# C210_0004_MAX_Module_220601.net
KiCad netlist of a schematic drawn in Altium Designer
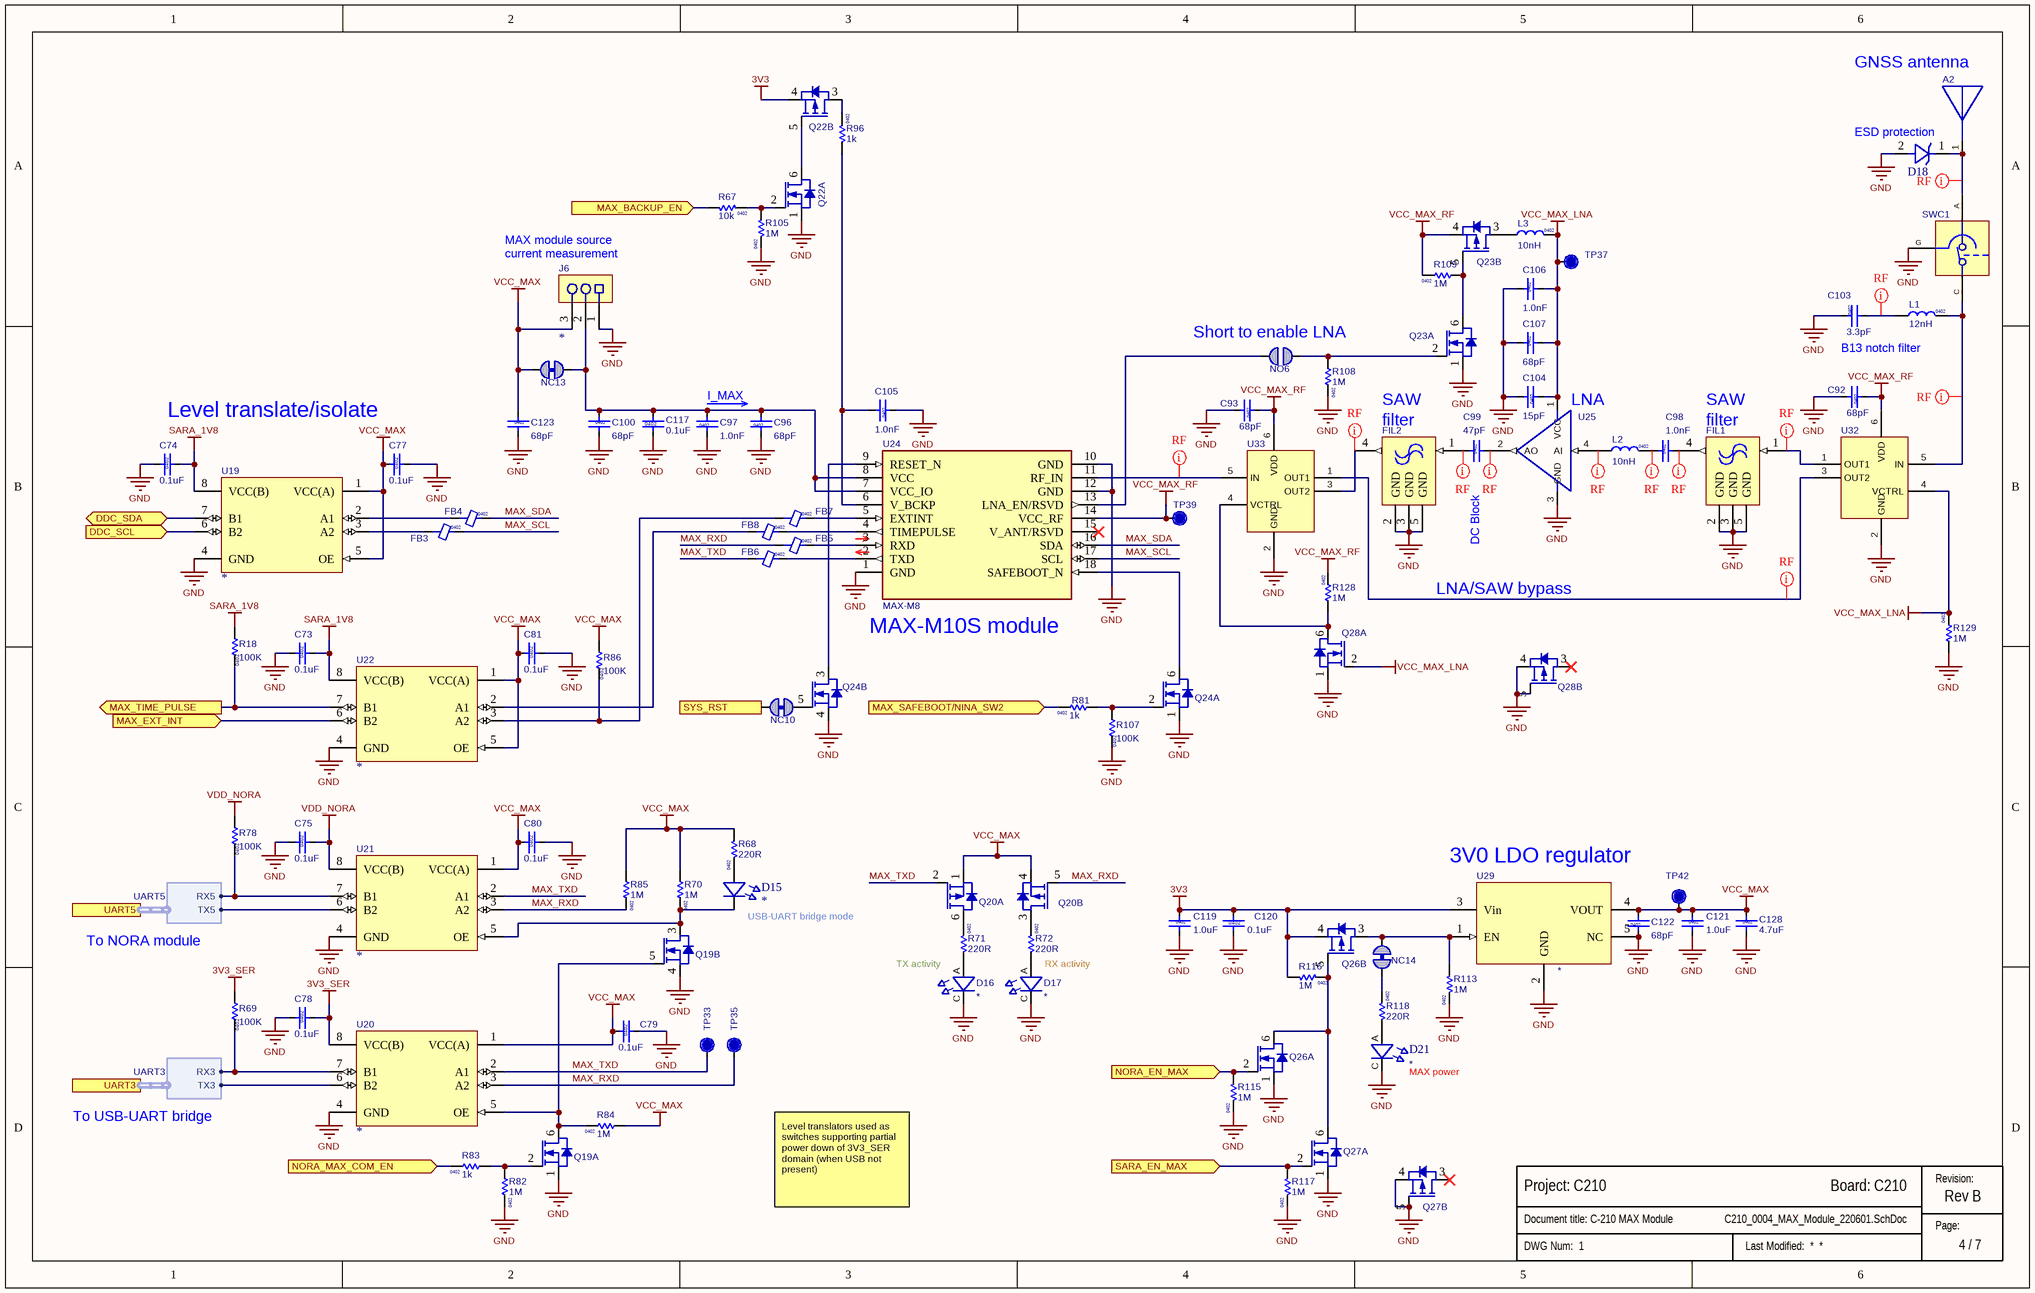
[diagram p0: C210_0004_MAX_Module_220601.SchDoc]

(export (version "E")
  (design (tool "Eeschema 10.0.6"))
  (components
    (comp (ref "A2")
      (value "CGGP.25.4.E.02")
      (footprint "CGGP.25.4.E.02")
      (description "ANT, THROUGH-HOLE, PATCH, GNSS, BEIDOU, GLONASS, GPS, 5dBi, 25MMx35MMx4MM")
      (libsource (lib "CGGP.25.4.E.02") (part "CGGP.25.4.E.02"))
    )
    (comp (ref "C73")
      (value "0.1uF")
      (footprint "Cap 0402 HD")
      (description "Cap, Ceramic 0.1uF 10V 10% X5R 0402")
      (fields
        (field (name "SIZE") "0402")
        (field (name "PART NUMBER") "120-00016")
        (field (name "MANUFACTURER") "Murata Electronics North America")
      )
      (libsource (lib "Arena_Parts_DB_Lib") (part "Cap Chip"))
    )
    (comp (ref "C74")
      (value "0.1uF")
      (footprint "Cap 0402 HD")
      (description "Cap, Ceramic 0.1uF 10V 10% X5R 0402")
      (fields
        (field (name "SIZE") "0402")
        (field (name "PART NUMBER") "120-00016")
        (field (name "MANUFACTURER") "Murata Electronics North America")
      )
      (libsource (lib "Arena_Parts_DB_Lib") (part "Cap Chip"))
    )
    (comp (ref "C75")
      (value "0.1uF")
      (footprint "Cap 0402 HD")
      (description "Cap, Ceramic 0.1uF 10V 10% X5R 0402")
      (fields
        (field (name "SIZE") "0402")
        (field (name "PART NUMBER") "120-00016")
        (field (name "MANUFACTURER") "Murata Electronics North America")
      )
      (libsource (lib "Arena_Parts_DB_Lib") (part "Cap Chip"))
    )
    (comp (ref "C77")
      (value "0.1uF")
      (footprint "Cap 0402 HD")
      (description "Cap, Ceramic 0.1uF 10V 10% X5R 0402")
      (fields
        (field (name "SIZE") "0402")
        (field (name "PART NUMBER") "120-00016")
        (field (name "MANUFACTURER") "Murata Electronics North America")
      )
      (libsource (lib "Arena_Parts_DB_Lib") (part "Cap Chip"))
    )
    (comp (ref "C78")
      (value "0.1uF")
      (footprint "Cap 0402 HD")
      (description "Cap, Ceramic 0.1uF 10V 10% X5R 0402")
      (fields
        (field (name "SIZE") "0402")
        (field (name "PART NUMBER") "120-00016")
        (field (name "MANUFACTURER") "Murata Electronics North America")
      )
      (libsource (lib "Arena_Parts_DB_Lib") (part "Cap Chip"))
    )
    (comp (ref "C79")
      (value "0.1uF")
      (footprint "Cap 0402 HD")
      (description "Cap, Ceramic 0.1uF 10V 10% X5R 0402")
      (fields
        (field (name "SIZE") "0402")
        (field (name "PART NUMBER") "120-00016")
        (field (name "MANUFACTURER") "Murata Electronics North America")
      )
      (libsource (lib "Arena_Parts_DB_Lib") (part "Cap Chip"))
    )
    (comp (ref "C80")
      (value "0.1uF")
      (footprint "Cap 0402 HD")
      (description "Cap, Ceramic 0.1uF 10V 10% X5R 0402")
      (fields
        (field (name "SIZE") "0402")
        (field (name "PART NUMBER") "120-00016")
        (field (name "MANUFACTURER") "Murata Electronics North America")
      )
      (libsource (lib "Arena_Parts_DB_Lib") (part "Cap Chip"))
    )
    (comp (ref "C81")
      (value "0.1uF")
      (footprint "Cap 0402 HD")
      (description "Cap, Ceramic 0.1uF 10V 10% X5R 0402")
      (fields
        (field (name "SIZE") "0402")
        (field (name "PART NUMBER") "120-00016")
        (field (name "MANUFACTURER") "Murata Electronics North America")
      )
      (libsource (lib "Arena_Parts_DB_Lib") (part "Cap Chip"))
    )
    (comp (ref "C92")
      (value "68pF")
      (footprint "Cap 0402 HD")
      (description "Cap, Ceramic, 68pF, 50V, 1%, NP0, 0402")
      (fields
        (field (name "SIZE") "0402")
        (field (name "PART NUMBER") "120-00047")
        (field (name "TOLERANCE") "+/- 1%")
      )
      (libsource (lib "Arena_Parts_DB_Lib") (part "Cap Chip"))
    )
    (comp (ref "C93")
      (value "68pF")
      (footprint "Cap 0402 HD")
      (description "Cap, Ceramic, 68pF, 50V, 1%, NP0, 0402")
      (fields
        (field (name "SIZE") "0402")
        (field (name "PART NUMBER") "120-00047")
        (field (name "TOLERANCE") "+/- 1%")
      )
      (libsource (lib "Arena_Parts_DB_Lib") (part "Cap Chip"))
    )
    (comp (ref "C96")
      (value "68pF")
      (footprint "Cap 0402 HD")
      (description "Cap, Ceramic, 68pF, 50V, 1%, NP0, 0402")
      (fields
        (field (name "SIZE") "0402")
        (field (name "PART NUMBER") "120-00047")
        (field (name "TOLERANCE") "+/- 1%")
      )
      (libsource (lib "Arena_Parts_DB_Lib") (part "Cap Chip"))
    )
    (comp (ref "C97")
      (value "1.0nF")
      (footprint "Cap 0402 HD")
      (description "CAP CER 1.0nF 50V 10% X7R 0402")
      (fields
        (field (name "SIZE") "0402")
        (field (name "PART NUMBER") "120-00010")
        (field (name "TOLERANCE") "+/- 10%")
      )
      (libsource (lib "Arena_Parts_DB_Lib") (part "Cap Chip"))
    )
    (comp (ref "C98")
      (value "1.0nF")
      (footprint "Cap 0402 HD")
      (description "CAP CER 1.0nF 50V 10% X7R 0402")
      (fields
        (field (name "SIZE") "0402")
        (field (name "PART NUMBER") "120-00010")
        (field (name "TOLERANCE") "+/- 10%")
      )
      (libsource (lib "Arena_Parts_DB_Lib") (part "Cap Chip"))
    )
    (comp (ref "C99")
      (value "47pF")
      (footprint "Cap 0402 HD")
      (description "Cap, Ceramic 47pF 50V 5% NP0 0402")
      (fields
        (field (name "SIZE") "0402")
        (field (name "PART NUMBER") "120-00081")
        (field (name "TOLERANCE") "+/- 5%")
      )
      (libsource (lib "Arena_Parts_DB_Lib") (part "Cap Chip"))
    )
    (comp (ref "C100")
      (value "68pF")
      (footprint "Cap 0402 HD")
      (description "Cap, Ceramic, 68pF, 50V, 1%, NP0, 0402")
      (fields
        (field (name "SIZE") "0402")
        (field (name "PART NUMBER") "120-00047")
        (field (name "TOLERANCE") "+/- 1%")
      )
      (libsource (lib "Arena_Parts_DB_Lib") (part "Cap Chip"))
    )
    (comp (ref "C103")
      (value "3.3pF")
      (footprint "Cap 0402 HD")
      (description "CAP CER 3.3PF 50V +/-0.25pF NP0 0402")
      (fields
        (field (name "SIZE") "0402")
        (field (name "PART NUMBER") "120-00079")
        (field (name "TOLERANCE") "Other")
      )
      (libsource (lib "Arena_Parts_DB_Lib") (part "Cap Chip"))
    )
    (comp (ref "C104")
      (value "15pF")
      (footprint "Cap 0402 HD")
      (description "Capacitor, Ceramic, 15pF 5%, 50V, NPO, 0402")
      (fields
        (field (name "SIZE") "0402")
        (field (name "PART NUMBER") "120-00110")
        (field (name "TOLERANCE") "+/- 5%")
      )
      (libsource (lib "Arena_Parts_DB_Lib") (part "Cap Chip"))
    )
    (comp (ref "C105")
      (value "1.0nF")
      (footprint "Cap 0402 HD")
      (description "CAP CER 1.0nF 50V 10% X7R 0402")
      (fields
        (field (name "SIZE") "0402")
        (field (name "PART NUMBER") "120-00010")
        (field (name "TOLERANCE") "+/- 10%")
      )
      (libsource (lib "Arena_Parts_DB_Lib") (part "Cap Chip"))
    )
    (comp (ref "C106")
      (value "1.0nF")
      (footprint "Cap 0402 HD")
      (description "CAP CER 1.0nF 50V 10% X7R 0402")
      (fields
        (field (name "SIZE") "0402")
        (field (name "PART NUMBER") "120-00010")
        (field (name "TOLERANCE") "+/- 10%")
      )
      (libsource (lib "Arena_Parts_DB_Lib") (part "Cap Chip"))
    )
    (comp (ref "C107")
      (value "68pF")
      (footprint "Cap 0402 HD")
      (description "Cap, Ceramic, 68pF, 50V, 1%, NP0, 0402")
      (fields
        (field (name "SIZE") "0402")
        (field (name "PART NUMBER") "120-00047")
        (field (name "TOLERANCE") "+/- 1%")
      )
      (libsource (lib "Arena_Parts_DB_Lib") (part "Cap Chip"))
    )
    (comp (ref "C117")
      (value "0.1uF")
      (footprint "Cap 0402 HD")
      (description "Cap, Ceramic 0.1uF 10V 10% X5R 0402")
      (fields
        (field (name "SIZE") "0402")
        (field (name "PART NUMBER") "120-00016")
        (field (name "MANUFACTURER") "Murata Electronics North America")
      )
      (libsource (lib "Arena_Parts_DB_Lib") (part "Cap Chip"))
    )
    (comp (ref "C119")
      (value "1.0uF")
      (footprint "Cap 0402 HD")
      (description "Cap, Ceramic, 1.0uF 10V 10% X5R, 0402")
      (fields
        (field (name "SIZE") "0402")
        (field (name "PART NUMBER") "120-00017")
        (field (name "MANUFACTURER") "Murata Electronics North America")
      )
      (libsource (lib "Arena_Parts_DB_Lib") (part "Cap Chip"))
    )
    (comp (ref "C120")
      (value "0.1uF")
      (footprint "Cap 0402 HD")
      (description "Cap, Ceramic 0.1uF 10V 10% X5R 0402")
      (fields
        (field (name "SIZE") "0402")
        (field (name "PART NUMBER") "120-00016")
        (field (name "MANUFACTURER") "Murata Electronics North America")
      )
      (libsource (lib "Arena_Parts_DB_Lib") (part "Cap Chip"))
    )
    (comp (ref "C121")
      (value "1.0uF")
      (footprint "Cap 0402 HD")
      (description "Cap, Ceramic, 1.0uF 10V 10% X5R, 0402")
      (fields
        (field (name "SIZE") "0402")
        (field (name "PART NUMBER") "120-00017")
        (field (name "MANUFACTURER") "Murata Electronics North America")
      )
      (libsource (lib "Arena_Parts_DB_Lib") (part "Cap Chip"))
    )
    (comp (ref "C122")
      (value "68pF")
      (footprint "Cap 0402 HD")
      (description "Cap, Ceramic, 68pF, 50V, 1%, NP0, 0402")
      (fields
        (field (name "SIZE") "0402")
        (field (name "PART NUMBER") "120-00047")
        (field (name "TOLERANCE") "+/- 1%")
      )
      (libsource (lib "Arena_Parts_DB_Lib") (part "Cap Chip"))
    )
    (comp (ref "C123")
      (value "68pF")
      (footprint "Cap 0402 HD")
      (description "Cap, Ceramic, 68pF, 50V, 1%, NP0, 0402")
      (fields
        (field (name "SIZE") "0402")
        (field (name "PART NUMBER") "120-00047")
        (field (name "TOLERANCE") "+/- 1%")
      )
      (libsource (lib "Arena_Parts_DB_Lib") (part "Cap Chip"))
    )
    (comp (ref "C128")
      (value "4.7uF")
      (footprint "Cap 0402 HD")
      (description "Cap, Ceramic 4.7uF 10V 20% X5R 0402")
      (fields
        (field (name "SIZE") "0402")
        (field (name "PART NUMBER") "120-00020")
        (field (name "TOLERANCE") "+/- 20%")
      )
      (libsource (lib "Arena_Parts_DB_Lib") (part "Cap Chip"))
    )
    (comp (ref "D15")
      (value "115-00023")
      (footprint "LED-0603")
      (description "LED BLUE DIFFUSED 0603 SMD")
      (fields (field (name "COLOR") "*") (field (name "VOLTAGE") "None"))
      (libsource (lib "Arena_Parts_DB_Lib") (part "LED_BASE"))
    )
    (comp (ref "D16")
      (value "115-00019")
      (footprint "LTST-C190KGKT")
      (description "DIODE, LED, SMT, GREEN, CLEAR LENS, 2.0V 20mA, 0603")
      (fields (field (name "VOLTAGE") "2.0V") (field (name "COLOR") "*"))
      (libsource (lib "LTST-C190KGKT") (part "LTST-C190KGKT"))
    )
    (comp (ref "D17")
      (value "LTST-C190YKT")
      (footprint "LTST-C190YKT")
      (description "DIODE, LED, SMT, YELLOW, CLEAR LENS, 2.1V 10mA, 0603")
      (fields (field (name "VOLTAGE") "2.1V") (field (name "COLOR") "*"))
      (libsource (lib "LTST-C190YKT") (part "LTST-C190YKT"))
    )
    (comp (ref "D18")
      (value "~")
      (footprint "SOD-923_2")
      (description "Diode, TVS, SMT, ESD9101P2T5G, 3.3V, 0.5pF, SOD-923")
      (fields (field (name "VOLTAGE") "3.3V"))
      (libsource (lib "ESD9101P2T5G") (part "ESD9101P2T5G"))
    )
    (comp (ref "D21")
      (value "LTST-C190EKT")
      (footprint "LTST-C190EKT")
      (description "DIODE, LED, SMT, Red, CLEAR LENS, 2.0V 10mA, 0603")
      (fields (field (name "VOLTAGE") "2.0V") (field (name "COLOR") "*"))
      (libsource (lib "LTST-C190EKT") (part "LTST-C190EKT"))
    )
    (comp (ref "FB3")
      (value "155-00003")
      (footprint "IND 0402")
      (description "Ferrite Bead, 1k Ohm @ 100MHz, 0402")
      (fields (field (name "SIZE") "0402") (field (name "VOLTAGE") "None"))
      (libsource (lib "Arena_Parts_DB_Lib") (part "FB sm"))
    )
    (comp (ref "FB4")
      (value "155-00003")
      (footprint "IND 0402")
      (description "Ferrite Bead, 1k Ohm @ 100MHz, 0402")
      (fields (field (name "SIZE") "0402") (field (name "VOLTAGE") "None"))
      (libsource (lib "Arena_Parts_DB_Lib") (part "FB sm"))
    )
    (comp (ref "FB5")
      (value "155-00003")
      (footprint "IND 0402")
      (description "Ferrite Bead, 1k Ohm @ 100MHz, 0402")
      (fields (field (name "SIZE") "0402") (field (name "VOLTAGE") "None"))
      (libsource (lib "Arena_Parts_DB_Lib") (part "FB sm"))
    )
    (comp (ref "FB6")
      (value "155-00003")
      (footprint "IND 0402")
      (description "Ferrite Bead, 1k Ohm @ 100MHz, 0402")
      (fields (field (name "SIZE") "0402") (field (name "VOLTAGE") "None"))
      (libsource (lib "Arena_Parts_DB_Lib") (part "FB sm"))
    )
    (comp (ref "FB7")
      (value "155-00003")
      (footprint "IND 0402")
      (description "Ferrite Bead, 1k Ohm @ 100MHz, 0402")
      (fields (field (name "SIZE") "0402") (field (name "VOLTAGE") "None"))
      (libsource (lib "Arena_Parts_DB_Lib") (part "FB sm"))
    )
    (comp (ref "FB8")
      (value "155-00003")
      (footprint "IND 0402")
      (description "Ferrite Bead, 1k Ohm @ 100MHz, 0402")
      (fields (field (name "SIZE") "0402") (field (name "VOLTAGE") "None"))
      (libsource (lib "Arena_Parts_DB_Lib") (part "FB sm"))
    )
    (comp (ref "FIL1")
      (value "B39162B4353P810")
      (footprint "QCS5P")
      (description "FILTER, SMT, SAW, GNSS, 1.559-1.606GHz, LGA5")
      (libsource (lib "B39162B4353P810") (part "B39162B4353P810"))
    )
    (comp (ref "FIL2")
      (value "B39162B4353P810")
      (footprint "QCS5P")
      (description "FILTER, SMT, SAW, GNSS, 1.559-1.606GHz, LGA5")
      (libsource (lib "B39162B4353P810") (part "B39162B4353P810"))
    )
    (comp (ref "J6")
      (value "130-00105")
      (footprint "HDR-0.1P-3Pin-1Row-SMT")
      (description "Header, 0.100\" Pitch, 3 Pin, Vertical SMT, Black")
      (fields (field (name "MANUFACTURER P/N") "*") (field (name "VOLTAGE") "None"))
      (libsource (lib "Arena_Parts_DB_Lib") (part "CON-3Pin_1Row"))
    )
    (comp (ref "L1")
      (value "12nH")
      (footprint "IND 0402 HD")
      (description "Inductor, 12nH, 300mA, 0402")
      (fields
        (field (name "SIZE") "0402")
        (field (name "PART NUMBER") "150-00028")
        (field (name "TOLERANCE") "+/- 5%")
      )
      (libsource (lib "Arena_Parts_DB_Lib") (part "Ind sm"))
    )
    (comp (ref "L2")
      (value "10nH")
      (footprint "IND 0402")
      (description "INDUCTOR 10NH 300MA 0402")
      (fields
        (field (name "SIZE") "0402")
        (field (name "PART NUMBER") "150-00010")
        (field (name "TOLERANCE") "+/- 5%")
      )
      (libsource (lib "Arena_Parts_DB_Lib") (part "Ind sm"))
    )
    (comp (ref "L3")
      (value "10nH")
      (footprint "IND 0402")
      (description "INDUCTOR 10NH 300MA 0402")
      (fields
        (field (name "SIZE") "0402")
        (field (name "PART NUMBER") "150-00010")
        (field (name "TOLERANCE") "+/- 5%")
      )
      (libsource (lib "Arena_Parts_DB_Lib") (part "Ind sm"))
    )
    (comp (ref "NC10")
      (value "Solderbridge-ShortDNP")
      (footprint "Solderbridge-Short")
      (description "Solderbridge-Short")
      (fields (field (name "ADDED BY") "Paul B"))
      (libsource (lib "PCB_Misc") (part "Solderbridge-Short"))
    )
    (comp (ref "NC13")
      (value "Solderbridge-ShortDNP")
      (footprint "Solderbridge-Short")
      (description "Solderbridge-Short")
      (fields (field (name "ADDED BY") "Paul B"))
      (libsource (lib "PCB_Misc") (part "Solderbridge-Short"))
    )
    (comp (ref "NC14")
      (value "Solderbridge-ShortDNP")
      (footprint "Solderbridge-Short")
      (description "Solderbridge-Short")
      (fields (field (name "ADDED BY") "Paul B"))
      (libsource (lib "") (part "Solderbridge-Short_1"))
    )
    (comp (ref "NO6")
      (value "Solderbridge-OpenDNP")
      (footprint "Solderbridge-Open")
      (description "Solderbridge-Open")
      (fields (field (name "ADDED BY") "Paul B"))
      (libsource (lib "PCB_Misc") (part "Solderbridge-Open"))
    )
    (comp (ref "Q19")
      (value "140-00016")
      (footprint "SOT-563")
      (description "MOSFET 2N-CH 20V 0.8A, SOT-563")
      (fields (field (name "VOLTAGE") "20V"))
      (libsource (lib "Arena_Parts_DB_Lib") (part "MOSFET-N-Dual"))
    )
    (comp (ref "Q20")
      (value "FDY2000PZ")
      (footprint "FDY2000PZ")
      (description "MOSFET DUAL P-CH 20V SOT-563, -350mA")
      (fields (field (name "VOLTAGE") "20V"))
      (libsource (lib "FDY2000PZ") (part "MOSFET-Dual-P_Chan"))
    )
    (comp (ref "Q22")
      (value "140-00030")
      (footprint "SOT-563")
      (description "MOSFET N/P-CH 20V SOT-563, 540 mA, −430 mA")
      (fields (field (name "VOLTAGE") "20V"))
      (libsource (lib "Arena_Parts_DB_Lib") (part "MOSFET-N-P_Pair"))
    )
    (comp (ref "Q23")
      (value "140-00030")
      (footprint "SOT-563")
      (description "MOSFET N/P-CH 20V SOT-563, 540 mA, −430 mA")
      (fields (field (name "VOLTAGE") "20V"))
      (libsource (lib "Arena_Parts_DB_Lib") (part "MOSFET-N-P_Pair"))
    )
    (comp (ref "Q24")
      (value "140-00016")
      (footprint "SOT-563")
      (description "MOSFET 2N-CH 20V 0.8A, SOT-563")
      (fields (field (name "VOLTAGE") "20V"))
      (libsource (lib "Arena_Parts_DB_Lib") (part "MOSFET-N-Dual"))
    )
    (comp (ref "Q26")
      (value "140-00030")
      (footprint "SOT-563")
      (description "MOSFET N/P-CH 20V SOT-563, 540 mA, −430 mA")
      (fields (field (name "VOLTAGE") "20V"))
      (libsource (lib "Arena_Parts_DB_Lib") (part "MOSFET-N-P_Pair"))
    )
    (comp (ref "Q27")
      (value "140-00030")
      (footprint "SOT-563")
      (description "MOSFET N/P-CH 20V SOT-563, 540 mA, −430 mA")
      (fields (field (name "VOLTAGE") "20V"))
      (libsource (lib "Arena_Parts_DB_Lib") (part "MOSFET-N-P_Pair"))
    )
    (comp (ref "Q28")
      (value "140-00030")
      (footprint "SOT-563")
      (description "MOSFET N/P-CH 20V SOT-563, 540 mA, −430 mA")
      (fields (field (name "VOLTAGE") "20V"))
      (libsource (lib "Arena_Parts_DB_Lib") (part "MOSFET-N-P_Pair"))
    )
    (comp (ref "R18")
      (value "100K")
      (footprint "RES 0402 HD")
      (description "Resistor 100K ohm 1% 1/16W, 0402")
      (fields
        (field (name "SIZE") "0402")
        (field (name "PART NUMBER") "180-00093")
        (field (name "POWER") "1/16W")
      )
      (libsource (lib "Arena_Parts_DB_Lib") (part "Res sm"))
    )
    (comp (ref "R67")
      (value "10k")
      (footprint "RES 0402 HD")
      (description "Resistor 10k ohm 1% 1/16W, 0402")
      (fields
        (field (name "SIZE") "0402")
        (field (name "PART NUMBER") "180-00024")
        (field (name "POWER") "1/16W")
      )
      (libsource (lib "Arena_Parts_DB_Lib") (part "Res sm"))
    )
    (comp (ref "R68")
      (value "220R")
      (footprint "RES 0402 HD")
      (description "Resistor, 220ohm, 5%, 1/16W, 0402.")
      (fields
        (field (name "SIZE") "0402")
        (field (name "PART NUMBER") "180-00098")
        (field (name "MANUFACTURER") "Panasonic Electronic Components")
      )
      (libsource (lib "Arena_Parts_DB_Lib") (part "Res sm"))
    )
    (comp (ref "R69")
      (value "100K")
      (footprint "RES 0402 HD")
      (description "Resistor 100K ohm 1% 1/16W, 0402")
      (fields
        (field (name "SIZE") "0402")
        (field (name "PART NUMBER") "180-00093")
        (field (name "POWER") "1/16W")
      )
      (libsource (lib "Arena_Parts_DB_Lib") (part "Res sm"))
    )
    (comp (ref "R70")
      (value "1M")
      (footprint "RES 0402 HD")
      (description "Resistor 1M ohm 1%, 1/16W, 0402")
      (fields
        (field (name "SIZE") "0402")
        (field (name "PART NUMBER") "180-00054")
        (field (name "POWER") "1/16W")
      )
      (libsource (lib "Arena_Parts_DB_Lib") (part "Res sm"))
    )
    (comp (ref "R71")
      (value "220R")
      (footprint "RES 0402 HD")
      (description "Resistor, 220ohm, 5%, 1/16W, 0402.")
      (fields
        (field (name "SIZE") "0402")
        (field (name "PART NUMBER") "180-00098")
        (field (name "MANUFACTURER") "Panasonic Electronic Components")
      )
      (libsource (lib "Arena_Parts_DB_Lib") (part "Res sm"))
    )
    (comp (ref "R72")
      (value "220R")
      (footprint "RES 0402 HD")
      (description "Resistor, 220ohm, 5%, 1/16W, 0402.")
      (fields
        (field (name "SIZE") "0402")
        (field (name "PART NUMBER") "180-00098")
        (field (name "MANUFACTURER") "Panasonic Electronic Components")
      )
      (libsource (lib "Arena_Parts_DB_Lib") (part "Res sm"))
    )
    (comp (ref "R78")
      (value "100K")
      (footprint "RES 0402 HD")
      (description "Resistor 100K ohm 1% 1/16W, 0402")
      (fields
        (field (name "SIZE") "0402")
        (field (name "PART NUMBER") "180-00093")
        (field (name "POWER") "1/16W")
      )
      (libsource (lib "Arena_Parts_DB_Lib") (part "Res sm"))
    )
    (comp (ref "R81")
      (value "1k")
      (footprint "RES 0402 HD")
      (description "Resistor 1k ohm 1% 1/16W, 0402")
      (fields
        (field (name "SIZE") "0402")
        (field (name "PART NUMBER") "180-00021")
        (field (name "POWER") "1/16W")
      )
      (libsource (lib "Arena_Parts_DB_Lib") (part "Res sm"))
    )
    (comp (ref "R82")
      (value "1M")
      (footprint "RES 0402 HD")
      (description "Resistor 1M ohm 1%, 1/16W, 0402")
      (fields
        (field (name "SIZE") "0402")
        (field (name "PART NUMBER") "180-00054")
        (field (name "POWER") "1/16W")
      )
      (libsource (lib "Arena_Parts_DB_Lib") (part "Res sm"))
    )
    (comp (ref "R83")
      (value "1k")
      (footprint "RES 0402 HD")
      (description "Resistor 1k ohm 1% 1/16W, 0402")
      (fields
        (field (name "SIZE") "0402")
        (field (name "PART NUMBER") "180-00021")
        (field (name "POWER") "1/16W")
      )
      (libsource (lib "Arena_Parts_DB_Lib") (part "Res sm"))
    )
    (comp (ref "R84")
      (value "1M")
      (footprint "RES 0402 HD")
      (description "Resistor 1M ohm 1%, 1/16W, 0402")
      (fields
        (field (name "SIZE") "0402")
        (field (name "PART NUMBER") "180-00054")
        (field (name "POWER") "1/16W")
      )
      (libsource (lib "Arena_Parts_DB_Lib") (part "Res sm"))
    )
    (comp (ref "R85")
      (value "1M")
      (footprint "RES 0402 HD")
      (description "Resistor 1M ohm 1%, 1/16W, 0402")
      (fields
        (field (name "SIZE") "0402")
        (field (name "PART NUMBER") "180-00054")
        (field (name "POWER") "1/16W")
      )
      (libsource (lib "Arena_Parts_DB_Lib") (part "Res sm"))
    )
    (comp (ref "R86")
      (value "100K")
      (footprint "RES 0402 HD")
      (description "Resistor 100K ohm 1% 1/16W, 0402")
      (fields
        (field (name "SIZE") "0402")
        (field (name "PART NUMBER") "180-00093")
        (field (name "POWER") "1/16W")
      )
      (libsource (lib "Arena_Parts_DB_Lib") (part "Res sm"))
    )
    (comp (ref "R96")
      (value "1k")
      (footprint "RES 0402 HD")
      (description "Resistor 1k ohm 1% 1/16W, 0402")
      (fields
        (field (name "SIZE") "0402")
        (field (name "PART NUMBER") "180-00021")
        (field (name "POWER") "1/16W")
      )
      (libsource (lib "Arena_Parts_DB_Lib") (part "Res sm"))
    )
    (comp (ref "R105")
      (value "1M")
      (footprint "RES 0402 HD")
      (description "Resistor 1M ohm 1%, 1/16W, 0402")
      (fields
        (field (name "SIZE") "0402")
        (field (name "PART NUMBER") "180-00054")
        (field (name "POWER") "1/16W")
      )
      (libsource (lib "Arena_Parts_DB_Lib") (part "Res sm"))
    )
    (comp (ref "R107")
      (value "100K")
      (footprint "RES 0402 HD")
      (description "Resistor 100K ohm 1% 1/16W, 0402")
      (fields
        (field (name "SIZE") "0402")
        (field (name "PART NUMBER") "180-00093")
        (field (name "POWER") "1/16W")
      )
      (libsource (lib "Arena_Parts_DB_Lib") (part "Res sm"))
    )
    (comp (ref "R108")
      (value "1M")
      (footprint "RES 0402 HD")
      (description "Resistor 1M ohm 1%, 1/16W, 0402")
      (fields
        (field (name "SIZE") "0402")
        (field (name "PART NUMBER") "180-00054")
        (field (name "POWER") "1/16W")
      )
      (libsource (lib "Arena_Parts_DB_Lib") (part "Res sm"))
    )
    (comp (ref "R109")
      (value "1M")
      (footprint "RES 0402 HD")
      (description "Resistor 1M ohm 1%, 1/16W, 0402")
      (fields
        (field (name "SIZE") "0402")
        (field (name "PART NUMBER") "180-00054")
        (field (name "POWER") "1/16W")
      )
      (libsource (lib "Arena_Parts_DB_Lib") (part "Res sm"))
    )
    (comp (ref "R113")
      (value "1M")
      (footprint "RES 0402 HD")
      (description "Resistor 1M ohm 1%, 1/16W, 0402")
      (fields
        (field (name "SIZE") "0402")
        (field (name "PART NUMBER") "180-00054")
        (field (name "POWER") "1/16W")
      )
      (libsource (lib "Arena_Parts_DB_Lib") (part "Res sm"))
    )
    (comp (ref "R115")
      (value "1M")
      (footprint "RES 0402 HD")
      (description "Resistor 1M ohm 1%, 1/16W, 0402")
      (fields
        (field (name "SIZE") "0402")
        (field (name "PART NUMBER") "180-00054")
        (field (name "POWER") "1/16W")
      )
      (libsource (lib "Arena_Parts_DB_Lib") (part "Res sm"))
    )
    (comp (ref "R116")
      (value "1M")
      (footprint "RES 0402 HD")
      (description "Resistor 1M ohm 1%, 1/16W, 0402")
      (fields
        (field (name "SIZE") "0402")
        (field (name "PART NUMBER") "180-00054")
        (field (name "POWER") "1/16W")
      )
      (libsource (lib "Arena_Parts_DB_Lib") (part "Res sm"))
    )
    (comp (ref "R117")
      (value "1M")
      (footprint "RES 0402 HD")
      (description "Resistor 1M ohm 1%, 1/16W, 0402")
      (fields
        (field (name "SIZE") "0402")
        (field (name "PART NUMBER") "180-00054")
        (field (name "POWER") "1/16W")
      )
      (libsource (lib "Arena_Parts_DB_Lib") (part "Res sm"))
    )
    (comp (ref "R118")
      (value "220R")
      (footprint "RES 0402 HD")
      (description "Resistor, 220ohm, 5%, 1/16W, 0402.")
      (fields
        (field (name "SIZE") "0402")
        (field (name "PART NUMBER") "180-00098")
        (field (name "MANUFACTURER") "Panasonic Electronic Components")
      )
      (libsource (lib "Arena_Parts_DB_Lib") (part "Res sm"))
    )
    (comp (ref "R128")
      (value "1M")
      (footprint "RES 0402 HD")
      (description "Resistor 1M ohm 1%, 1/16W, 0402")
      (fields
        (field (name "SIZE") "0402")
        (field (name "PART NUMBER") "180-00054")
        (field (name "POWER") "1/16W")
      )
      (libsource (lib "Arena_Parts_DB_Lib") (part "Res sm"))
    )
    (comp (ref "R129")
      (value "1M")
      (footprint "RES 0402 HD")
      (description "Resistor 1M ohm 1%, 1/16W, 0402")
      (fields
        (field (name "SIZE") "0402")
        (field (name "PART NUMBER") "180-00054")
        (field (name "POWER") "1/16W")
      )
      (libsource (lib "Arena_Parts_DB_Lib") (part "Res sm"))
    )
    (comp (ref "SWC1")
      (value "MS-156C3")
      (footprint "MS-156C3")
      (description "Conn, Coax, Test, Switch, 50Ohm, SMT, 2.5mmX2.4mm")
      (fields (field (name "VOLTAGE") "None"))
      (libsource (lib "MS-156C3") (part "MS-156C3"))
    )
    (comp (ref "TP33")
      (value "TP")
      (footprint "TP12R")
      (description "Testpoint, Round 1.0mm Dia")
      (fields
        (field (name "PART NUMBER") "TP10R")
        (field (name "ADDED BY") "Jeremy D")
        (field (name "CHECKED BY") "Paul B")
      )
      (libsource (lib "PCB_Misc") (part "TP_R"))
    )
    (comp (ref "TP35")
      (value "TP")
      (footprint "TP12R")
      (description "Testpoint, Round 1.0mm Dia")
      (fields
        (field (name "PART NUMBER") "TP10R")
        (field (name "ADDED BY") "Jeremy D")
        (field (name "CHECKED BY") "Paul B")
      )
      (libsource (lib "PCB_Misc") (part "TP_R"))
    )
    (comp (ref "TP37")
      (value "TP")
      (footprint "TP12R")
      (description "Testpoint, Round 1.0mm Dia")
      (fields
        (field (name "PART NUMBER") "TP10R")
        (field (name "ADDED BY") "Jeremy D")
        (field (name "CHECKED BY") "Paul B")
      )
      (libsource (lib "PCB_Misc") (part "TP_R"))
    )
    (comp (ref "TP39")
      (value "TP")
      (footprint "TP12R")
      (description "Testpoint, Round 1.0mm Dia")
      (fields
        (field (name "PART NUMBER") "TP10R")
        (field (name "ADDED BY") "Jeremy D")
        (field (name "CHECKED BY") "Paul B")
      )
      (libsource (lib "PCB_Misc") (part "TP_R"))
    )
    (comp (ref "TP42")
      (value "TP")
      (footprint "TP12R")
      (description "Testpoint, Round 1.0mm Dia")
      (fields
        (field (name "PART NUMBER") "TP10R")
        (field (name "ADDED BY") "Jeremy D")
        (field (name "CHECKED BY") "Paul B")
      )
      (libsource (lib "PCB_Misc") (part "TP_R"))
    )
    (comp (ref "U19")
      (value "225-00008")
      (footprint "QFN0.4P3x1-8Pin")
      (description "IC Dual Translating Transceiver, 8XQFN")
      (fields (field (name "MANUFACTURER P/N") "*") (field (name "VOLTAGE") "5.5V"))
      (libsource (lib "Arena_Parts_DB_Lib") (part "NTSX2102GU8H"))
    )
    (comp (ref "U20")
      (value "225-00008")
      (footprint "QFN0.4P3x1-8Pin")
      (description "IC Dual Translating Transceiver, 8XQFN")
      (fields (field (name "MANUFACTURER P/N") "*") (field (name "VOLTAGE") "5.5V"))
      (libsource (lib "Arena_Parts_DB_Lib") (part "NTSX2102GU8H"))
    )
    (comp (ref "U21")
      (value "225-00008")
      (footprint "QFN0.4P3x1-8Pin")
      (description "IC Dual Translating Transceiver, 8XQFN")
      (fields (field (name "MANUFACTURER P/N") "*") (field (name "VOLTAGE") "5.5V"))
      (libsource (lib "Arena_Parts_DB_Lib") (part "NTSX2102GU8H"))
    )
    (comp (ref "U22")
      (value "225-00008")
      (footprint "QFN0.4P3x1-8Pin")
      (description "IC Dual Translating Transceiver, 8XQFN")
      (fields (field (name "MANUFACTURER P/N") "*") (field (name "VOLTAGE") "5.5V"))
      (libsource (lib "Arena_Parts_DB_Lib") (part "NTSX2102GU8H"))
    )
    (comp (ref "U24")
      (value "MAX-M8")
      (footprint "MAX-M8")
      (description "u-blox MAX GNSS module")
      (fields (field (name "MANUFACTURER") "u-blox"))
      (libsource (lib "ubloxLib") (part "MAX"))
    )
    (comp (ref "U25")
      (value "BGA123L4")
      (footprint "BGA0.4P2x2-4Pin")
      (description "LNA, SMT, GNSS, 1.1-3.6V, 1.1mA18dB, 0.75dB, BGA4")
      (fields (field (name "VOLTAGE") "1.1-3.6V"))
      (libsource (lib "BGA123L4") (part "BGA123L4"))
    )
    (comp (ref "U29")
      (value "260-00027")
      (footprint "SOT-553")
      (description "LDO, 3.0V, 200mA, SOT-5")
      (fields (field (name "MANUFACTURER P/N") "*") (field (name "VOLTAGE") "6.0V"))
      (libsource (lib "Arena_Parts_DB_Lib") (part "LDO_5Pin_TCR2LE"))
    )
    (comp (ref "U32")
      (value "SKY13585-679LF:")
      (footprint "SKY13585-679LF")
      (description "RF SWITCH, SPDT, I2C, 3-AXIS, 3-5V, 1-6GHz, SMT, DFN-6, 1mmX1mm")
      (fields (field (name "VOLTAGE") "1.9-3.6V"))
      (libsource (lib "") (part "SKY13585-679LF{colon}_1"))
    )
    (comp (ref "U33")
      (value "SKY13585-679LF:")
      (footprint "SKY13585-679LF")
      (description "RF SWITCH, SPDT, I2C, 3-AXIS, 3-5V, 1-6GHz, SMT, DFN-6, 1mmX1mm")
      (fields (field (name "VOLTAGE") "1.9-3.6V"))
      (libsource (lib "SKY13585-679LF") (part "SKY13585-679LF{colon}"))
    )
  )
  (nets
    (net (code "3") (name "/DDC_SCL") (class "Default")
      (node (ref "U19") (pin "6") (pinfunction "B2_6") (pintype "bidirectional"))
    )
    (net (code "4") (name "/DDC_SDA") (class "Default")
      (node (ref "U19") (pin "7") (pinfunction "B1_7") (pintype "bidirectional"))
    )
    (net (code "5") (name "/MAX_BACKUP_EN") (class "Default")
      (node (ref "R67") (pin "1") (pinfunction "1_1") (pintype "passive"))
    )
    (net (code "6") (name "/MAX_EXT_INT") (class "Default")
      (node (ref "U22") (pin "6") (pinfunction "B2_6") (pintype "bidirectional"))
    )
    (net (code "7") (name "/MAX_RXD") (class "Default")
      (node (ref "FB5") (pin "1") (pinfunction "1_1") (pintype "passive"))
      (node (ref "Q20") (pin "5") (pinfunction "G2_5") (pintype "passive"))
      (node (ref "R85") (pin "2") (pinfunction "2_2") (pintype "passive"))
      (node (ref "TP35") (pin "1") (pintype "passive"))
      (node (ref "U20") (pin "3") (pinfunction "A2_3") (pintype "bidirectional"))
      (node (ref "U21") (pin "3") (pinfunction "A2_3") (pintype "bidirectional"))
    )
    (net (code "8") (name "/MAX_SAFEBOOT{slash}NINA_SW2") (class "Default")
      (node (ref "R81") (pin "2") (pinfunction "2_2") (pintype "passive"))
    )
    (net (code "9") (name "/MAX_SCL") (class "Default")
      (node (ref "FB3") (pin "2") (pinfunction "2_2") (pintype "passive"))
      (node (ref "U24") (pin "17") (pinfunction "SCL_17") (pintype "bidirectional"))
    )
    (net (code "10") (name "/MAX_SDA") (class "Default")
      (node (ref "FB4") (pin "2") (pinfunction "2_2") (pintype "passive"))
      (node (ref "U24") (pin "16") (pinfunction "SDA_16") (pintype "bidirectional"))
    )
    (net (code "11") (name "/MAX_TIME_PULSE") (class "Default")
      (node (ref "R18") (pin "2") (pinfunction "2_2") (pintype "passive"))
      (node (ref "U22") (pin "7") (pinfunction "B1_7") (pintype "bidirectional"))
    )
    (net (code "12") (name "/MAX_TXD") (class "Default")
      (node (ref "FB6") (pin "1") (pinfunction "1_1") (pintype "passive"))
      (node (ref "Q20") (pin "2") (pinfunction "G1_2") (pintype "passive"))
      (node (ref "TP33") (pin "1") (pintype "passive"))
      (node (ref "U20") (pin "2") (pinfunction "A1_2") (pintype "bidirectional"))
      (node (ref "U21") (pin "2") (pinfunction "A1_2") (pintype "bidirectional"))
    )
    (net (code "13") (name "/NORA_EN_MAX") (class "Default")
      (node (ref "Q26") (pin "2") (pinfunction "G1_2") (pintype "passive"))
      (node (ref "R115") (pin "1") (pinfunction "1_1") (pintype "passive"))
    )
    (net (code "14") (name "/NORA_MAX_COM_EN") (class "Default")
      (node (ref "R83") (pin "2") (pinfunction "2_2") (pintype "passive"))
    )
    (net (code "15") (name "/RX3") (class "Default")
      (node (ref "R69") (pin "2") (pinfunction "2_2") (pintype "passive"))
      (node (ref "U20") (pin "7") (pinfunction "B1_7") (pintype "bidirectional"))
    )
    (net (code "16") (name "/RX5") (class "Default")
      (node (ref "R78") (pin "2") (pinfunction "2_2") (pintype "passive"))
      (node (ref "U21") (pin "7") (pinfunction "B1_7") (pintype "bidirectional"))
    )
    (net (code "17") (name "/SARA_EN_MAX") (class "Default")
      (node (ref "Q27") (pin "2") (pinfunction "G1_2") (pintype "passive"))
      (node (ref "R117") (pin "1") (pinfunction "1_1") (pintype "passive"))
    )
    (net (code "18") (name "/SYS_RST") (class "Default")
      (node (ref "NC10") (pin "2") (pinfunction "2_2") (pintype "passive"))
    )
    (net (code "19") (name "/TX3") (class "Default")
      (node (ref "U20") (pin "6") (pinfunction "B2_6") (pintype "bidirectional"))
    )
    (net (code "20") (name "/TX5") (class "Default")
      (node (ref "U21") (pin "6") (pinfunction "B2_6") (pintype "bidirectional"))
    )
    (net (code "23") (name "3V3") (class "Default")
      (node (ref "C119") (pin "1") (pinfunction "1_1") (pintype "passive"))
      (node (ref "C120") (pin "1") (pinfunction "1_1") (pintype "passive"))
      (node (ref "Q22") (pin "4") (pinfunction "S2_4") (pintype "passive"))
      (node (ref "Q26") (pin "4") (pinfunction "S2_4") (pintype "passive"))
      (node (ref "R116") (pin "1") (pinfunction "1_1") (pintype "passive"))
      (node (ref "U29") (pin "3") (pinfunction "Vin_3") (pintype "power_in"))
    )
    (net (code "24") (name "3V3_SER") (class "Default")
      (node (ref "C78") (pin "2") (pinfunction "2_2") (pintype "passive"))
      (node (ref "R69") (pin "1") (pinfunction "1_1") (pintype "passive"))
      (node (ref "U20") (pin "8") (pinfunction "VCC(B)_8") (pintype "power_in"))
    )
    (net (code "25") (name "GND") (class "Default")
      (node (ref "C100") (pin "2") (pinfunction "2_2") (pintype "passive"))
      (node (ref "C103") (pin "1") (pinfunction "1_1") (pintype "passive"))
      (node (ref "C104") (pin "2") (pinfunction "2_2") (pintype "passive"))
      (node (ref "C105") (pin "1") (pinfunction "1_1") (pintype "passive"))
      (node (ref "C106") (pin "1") (pinfunction "1_1") (pintype "passive"))
      (node (ref "C107") (pin "1") (pinfunction "1_1") (pintype "passive"))
      (node (ref "C117") (pin "1") (pinfunction "1_1") (pintype "passive"))
      (node (ref "C119") (pin "2") (pinfunction "2_2") (pintype "passive"))
      (node (ref "C120") (pin "2") (pinfunction "2_2") (pintype "passive"))
      (node (ref "C121") (pin "2") (pinfunction "2_2") (pintype "passive"))
      (node (ref "C122") (pin "1") (pinfunction "1_1") (pintype "passive"))
      (node (ref "C123") (pin "2") (pinfunction "2_2") (pintype "passive"))
      (node (ref "C128") (pin "2") (pinfunction "2_2") (pintype "passive"))
      (node (ref "C73") (pin "1") (pinfunction "1_1") (pintype "passive"))
      (node (ref "C74") (pin "1") (pinfunction "1_1") (pintype "passive"))
      (node (ref "C75") (pin "1") (pinfunction "1_1") (pintype "passive"))
      (node (ref "C77") (pin "2") (pinfunction "2_2") (pintype "passive"))
      (node (ref "C78") (pin "1") (pinfunction "1_1") (pintype "passive"))
      (node (ref "C79") (pin "2") (pinfunction "2_2") (pintype "passive"))
      (node (ref "C80") (pin "2") (pinfunction "2_2") (pintype "passive"))
      (node (ref "C81") (pin "2") (pinfunction "2_2") (pintype "passive"))
      (node (ref "C92") (pin "2") (pinfunction "2_2") (pintype "passive"))
      (node (ref "C93") (pin "2") (pinfunction "2_2") (pintype "passive"))
      (node (ref "C96") (pin "1") (pinfunction "1_1") (pintype "passive"))
      (node (ref "C97") (pin "1") (pinfunction "1_1") (pintype "passive"))
      (node (ref "D16") (pin "C") (pinfunction "Cathode_C") (pintype "passive"))
      (node (ref "D17") (pin "C") (pinfunction "Cathode_C") (pintype "passive"))
      (node (ref "D18") (pin "2") (pintype "passive"))
      (node (ref "D21") (pin "C") (pinfunction "Cathode_C") (pintype "passive"))
      (node (ref "FIL1") (pin "2") (pinfunction "GND_2") (pintype "power_in"))
      (node (ref "FIL1") (pin "3") (pinfunction "GND_3") (pintype "power_in"))
      (node (ref "FIL1") (pin "5") (pinfunction "GND_5") (pintype "power_in"))
      (node (ref "FIL2") (pin "2") (pinfunction "GND_2") (pintype "power_in"))
      (node (ref "FIL2") (pin "3") (pinfunction "GND_3") (pintype "power_in"))
      (node (ref "FIL2") (pin "5") (pinfunction "GND_5") (pintype "power_in"))
      (node (ref "J6") (pin "1") (pinfunction "1_1") (pintype "passive"))
      (node (ref "Q19") (pin "1") (pinfunction "S1_1") (pintype "passive"))
      (node (ref "Q19") (pin "4") (pinfunction "S2_4") (pintype "passive"))
      (node (ref "Q22") (pin "1") (pinfunction "S1_1") (pintype "passive"))
      (node (ref "Q23") (pin "1") (pinfunction "S1_1") (pintype "passive"))
      (node (ref "Q24") (pin "1") (pinfunction "S1_1") (pintype "passive"))
      (node (ref "Q24") (pin "4") (pinfunction "S2_4") (pintype "passive"))
      (node (ref "Q26") (pin "1") (pinfunction "S1_1") (pintype "passive"))
      (node (ref "Q27") (pin "1") (pinfunction "S1_1") (pintype "passive"))
      (node (ref "Q27") (pin "4") (pinfunction "S2_4") (pintype "passive"))
      (node (ref "Q27") (pin "5") (pinfunction "G2_5") (pintype "passive"))
      (node (ref "Q28") (pin "1") (pinfunction "S1_1") (pintype "passive"))
      (node (ref "Q28") (pin "4") (pinfunction "S2_4") (pintype "passive"))
      (node (ref "Q28") (pin "5") (pinfunction "G2_5") (pintype "passive"))
      (node (ref "R105") (pin "2") (pinfunction "2_2") (pintype "passive"))
      (node (ref "R107") (pin "2") (pinfunction "2_2") (pintype "passive"))
      (node (ref "R108") (pin "2") (pinfunction "2_2") (pintype "passive"))
      (node (ref "R113") (pin "2") (pinfunction "2_2") (pintype "passive"))
      (node (ref "R115") (pin "2") (pinfunction "2_2") (pintype "passive"))
      (node (ref "R117") (pin "2") (pinfunction "2_2") (pintype "passive"))
      (node (ref "R129") (pin "1") (pinfunction "1_1") (pintype "passive"))
      (node (ref "R82") (pin "2") (pinfunction "2_2") (pintype "passive"))
      (node (ref "SWC1") (pin "G") (pinfunction "G_G") (pintype "passive"))
      (node (ref "U19") (pin "4") (pinfunction "GND_4") (pintype "power_in"))
      (node (ref "U20") (pin "4") (pinfunction "GND_4") (pintype "power_in"))
      (node (ref "U21") (pin "4") (pinfunction "GND_4") (pintype "power_in"))
      (node (ref "U22") (pin "4") (pinfunction "GND_4") (pintype "power_in"))
      (node (ref "U24") (pin "1") (pinfunction "GND_1") (pintype "power_in"))
      (node (ref "U24") (pin "10") (pinfunction "GND_10") (pintype "power_in"))
      (node (ref "U24") (pin "12") (pinfunction "GND_12") (pintype "power_in"))
      (node (ref "U25") (pin "3") (pinfunction "GND_3") (pintype "power_in"))
      (node (ref "U29") (pin "2") (pinfunction "GND_2") (pintype "power_in"))
      (node (ref "U29") (pin "5") (pinfunction "NC_5") (pintype "passive"))
      (node (ref "U32") (pin "2") (pinfunction "GND_2") (pintype "power_in"))
      (node (ref "U33") (pin "2") (pinfunction "GND_2") (pintype "power_in"))
    )
    (net (code "26") (name "Net-(A2-Pad1)") (class "Default")
      (node (ref "A2") (pin "1") (pinfunction "1_1") (pintype "passive"))
      (node (ref "D18") (pin "1") (pintype "passive"))
      (node (ref "SWC1") (pin "A") (pinfunction "A_A") (pintype "passive"))
    )
    (net (code "27") (name "Net-(C98-Pad1)") (class "Default")
      (node (ref "C98") (pin "1") (pinfunction "1_1") (pintype "passive"))
      (node (ref "L2") (pin "2") (pinfunction "2_2") (pintype "passive"))
    )
    (net (code "28") (name "Net-(C103-Pad2)") (class "Default")
      (node (ref "C103") (pin "2") (pinfunction "2_2") (pintype "passive"))
      (node (ref "L1") (pin "1") (pinfunction "1_1") (pintype "passive"))
    )
    (net (code "29") (name "Net-(D15-A)") (class "Default")
      (node (ref "D15") (pin "2") (pinfunction "A_2") (pintype "passive"))
      (node (ref "R68") (pin "2") (pinfunction "2_2") (pintype "passive"))
    )
    (net (code "30") (name "Net-(D15-C)") (class "Default")
      (node (ref "D15") (pin "1") (pinfunction "C_1") (pintype "passive"))
      (node (ref "Q19") (pin "3") (pinfunction "D2_3") (pintype "passive"))
      (node (ref "R70") (pin "2") (pinfunction "2_2") (pintype "passive"))
      (node (ref "U21") (pin "5") (pinfunction "OE_5") (pintype "input"))
    )
    (net (code "31") (name "Net-(D16-Anode)") (class "Default")
      (node (ref "D16") (pin "A") (pinfunction "Anode_A") (pintype "passive"))
      (node (ref "R71") (pin "1") (pinfunction "1_1") (pintype "passive"))
    )
    (net (code "32") (name "Net-(D17-Anode)") (class "Default")
      (node (ref "D17") (pin "A") (pinfunction "Anode_A") (pintype "passive"))
      (node (ref "R72") (pin "1") (pinfunction "1_1") (pintype "passive"))
    )
    (net (code "33") (name "Net-(D21-Anode)") (class "Default")
      (node (ref "D21") (pin "A") (pinfunction "Anode_A") (pintype "passive"))
      (node (ref "R118") (pin "1") (pinfunction "1_1") (pintype "passive"))
    )
    (net (code "34") (name "Net-(FIL1-Input)") (class "Default")
      (node (ref "FIL1") (pin "1") (pinfunction "Input_1") (pintype "input"))
      (node (ref "U32") (pin "1") (pinfunction "OUT1_1") (pintype "passive"))
    )
    (net (code "35") (name "Net-(FIL1-Output)") (class "Default")
      (node (ref "C98") (pin "2") (pinfunction "2_2") (pintype "passive"))
      (node (ref "FIL1") (pin "4") (pinfunction "Output_4") (pintype "output"))
    )
    (net (code "36") (name "Net-(FIL2-Input)") (class "Default")
      (node (ref "C99") (pin "1") (pinfunction "1_1") (pintype "passive"))
      (node (ref "FIL2") (pin "1") (pinfunction "Input_1") (pintype "input"))
    )
    (net (code "37") (name "Net-(FIL2-Output)") (class "Default")
      (node (ref "FIL2") (pin "4") (pinfunction "Output_4") (pintype "output"))
      (node (ref "U33") (pin "3") (pinfunction "OUT2_3") (pintype "passive"))
    )
    (net (code "38") (name "Net-(NC14-Pad2)") (class "Default")
      (node (ref "NC14") (pin "2") (pinfunction "2_2") (pintype "passive"))
      (node (ref "R118") (pin "2") (pinfunction "2_2") (pintype "passive"))
    )
    (net (code "39") (name "Net-(Q19A-D1)") (class "Default")
      (node (ref "Q19") (pin "5") (pinfunction "G2_5") (pintype "passive"))
      (node (ref "Q19") (pin "6") (pinfunction "D1_6") (pintype "passive"))
      (node (ref "R84") (pin "2") (pinfunction "2_2") (pintype "passive"))
      (node (ref "U20") (pin "5") (pinfunction "OE_5") (pintype "input"))
    )
    (net (code "40") (name "Net-(Q19A-G1)") (class "Default")
      (node (ref "Q19") (pin "2") (pinfunction "G1_2") (pintype "passive"))
      (node (ref "R82") (pin "1") (pinfunction "1_1") (pintype "passive"))
      (node (ref "R83") (pin "1") (pinfunction "1_1") (pintype "passive"))
    )
    (net (code "41") (name "Net-(Q20A-D1)") (class "Default")
      (node (ref "Q20") (pin "6") (pinfunction "D1_6") (pintype "passive"))
      (node (ref "R71") (pin "2") (pinfunction "2_2") (pintype "passive"))
    )
    (net (code "42") (name "Net-(Q20B-D2)") (class "Default")
      (node (ref "Q20") (pin "3") (pinfunction "D2_3") (pintype "passive"))
      (node (ref "R72") (pin "2") (pinfunction "2_2") (pintype "passive"))
    )
    (net (code "43") (name "Net-(Q22A-D1)") (class "Default")
      (node (ref "Q22") (pin "5") (pinfunction "G2_5") (pintype "passive"))
      (node (ref "Q22") (pin "6") (pinfunction "D1_6") (pintype "passive"))
    )
    (net (code "44") (name "Net-(Q22A-G1)") (class "Default")
      (node (ref "Q22") (pin "2") (pinfunction "G1_2") (pintype "passive"))
      (node (ref "R105") (pin "1") (pinfunction "1_1") (pintype "passive"))
      (node (ref "R67") (pin "2") (pinfunction "2_2") (pintype "passive"))
    )
    (net (code "45") (name "Net-(Q22B-D2)") (class "Default")
      (node (ref "Q22") (pin "3") (pinfunction "D2_3") (pintype "passive"))
      (node (ref "R96") (pin "2") (pinfunction "2_2") (pintype "passive"))
    )
    (net (code "46") (name "Net-(Q23A-D1)") (class "Default")
      (node (ref "Q23") (pin "5") (pinfunction "G2_5") (pintype "passive"))
      (node (ref "Q23") (pin "6") (pinfunction "D1_6") (pintype "passive"))
      (node (ref "R109") (pin "1") (pinfunction "1_1") (pintype "passive"))
    )
    (net (code "47") (name "Net-(Q23A-G1)") (class "Default")
      (node (ref "NO6") (pin "2") (pinfunction "2_2") (pintype "passive"))
      (node (ref "Q23") (pin "2") (pinfunction "G1_2") (pintype "passive"))
      (node (ref "R108") (pin "1") (pinfunction "1_1") (pintype "passive"))
    )
    (net (code "48") (name "Net-(Q23B-D2)") (class "Default")
      (node (ref "L3") (pin "1") (pinfunction "1_1") (pintype "passive"))
      (node (ref "Q23") (pin "3") (pinfunction "D2_3") (pintype "passive"))
    )
    (net (code "49") (name "Net-(Q24A-D1)") (class "Default")
      (node (ref "Q24") (pin "6") (pinfunction "D1_6") (pintype "passive"))
      (node (ref "U24") (pin "18") (pinfunction "SAFEBOOT_N_18") (pintype "input"))
    )
    (net (code "50") (name "Net-(Q24A-G1)") (class "Default")
      (node (ref "Q24") (pin "2") (pinfunction "G1_2") (pintype "passive"))
      (node (ref "R107") (pin "1") (pinfunction "1_1") (pintype "passive"))
      (node (ref "R81") (pin "1") (pinfunction "1_1") (pintype "passive"))
    )
    (net (code "51") (name "Net-(Q24B-D2)") (class "Default")
      (node (ref "Q24") (pin "3") (pinfunction "D2_3") (pintype "passive"))
      (node (ref "U24") (pin "9") (pinfunction "RESET_N_9") (pintype "input"))
    )
    (net (code "52") (name "Net-(Q24B-G2)") (class "Default")
      (node (ref "NC10") (pin "1") (pinfunction "1_1") (pintype "passive"))
      (node (ref "Q24") (pin "5") (pinfunction "G2_5") (pintype "passive"))
    )
    (net (code "53") (name "Net-(Q26A-D1)") (class "Default")
      (node (ref "Q26") (pin "5") (pinfunction "G2_5") (pintype "passive"))
      (node (ref "Q26") (pin "6") (pinfunction "D1_6") (pintype "passive"))
      (node (ref "Q27") (pin "6") (pinfunction "D1_6") (pintype "passive"))
      (node (ref "R116") (pin "2") (pinfunction "2_2") (pintype "passive"))
    )
    (net (code "54") (name "Net-(Q26B-D2)") (class "Default")
      (node (ref "NC14") (pin "1") (pinfunction "1_1") (pintype "passive"))
      (node (ref "Q26") (pin "3") (pinfunction "D2_3") (pintype "passive"))
      (node (ref "R113") (pin "1") (pinfunction "1_1") (pintype "passive"))
      (node (ref "U29") (pin "1") (pinfunction "EN_1") (pintype "input"))
    )
    (net (code "55") (name "Net-(Q28A-D1)") (class "Default")
      (node (ref "Q28") (pin "6") (pinfunction "D1_6") (pintype "passive"))
      (node (ref "R128") (pin "1") (pinfunction "1_1") (pintype "passive"))
      (node (ref "U33") (pin "4") (pinfunction "VCTRL_4") (pintype "power_in"))
    )
    (net (code "56") (name "Net-(U19-A1)") (class "Default")
      (node (ref "FB4") (pin "1") (pinfunction "1_1") (pintype "passive"))
      (node (ref "U19") (pin "2") (pinfunction "A1_2") (pintype "bidirectional"))
    )
    (net (code "57") (name "Net-(U19-A2)") (class "Default")
      (node (ref "FB3") (pin "1") (pinfunction "1_1") (pintype "passive"))
      (node (ref "U19") (pin "3") (pinfunction "A2_3") (pintype "bidirectional"))
    )
    (net (code "58") (name "Net-(U22-A1)") (class "Default")
      (node (ref "FB8") (pin "1") (pinfunction "1_1") (pintype "passive"))
      (node (ref "U22") (pin "2") (pinfunction "A1_2") (pintype "bidirectional"))
    )
    (net (code "59") (name "Net-(U22-A2)") (class "Default")
      (node (ref "FB7") (pin "1") (pinfunction "1_1") (pintype "passive"))
      (node (ref "R86") (pin "2") (pinfunction "2_2") (pintype "passive"))
      (node (ref "U22") (pin "3") (pinfunction "A2_3") (pintype "bidirectional"))
    )
    (net (code "60") (name "Net-(U24-EXTINT)") (class "Default")
      (node (ref "FB7") (pin "2") (pinfunction "2_2") (pintype "passive"))
      (node (ref "U24") (pin "5") (pinfunction "EXTINT_5") (pintype "input"))
    )
    (net (code "61") (name "Net-(U24-LNA_EN{slash}RSVD)") (class "Default")
      (node (ref "NO6") (pin "1") (pinfunction "1_1") (pintype "passive"))
      (node (ref "U24") (pin "13") (pinfunction "LNA_EN/RSVD_13") (pintype "output"))
    )
    (net (code "62") (name "Net-(U24-RF_IN)") (class "Default")
      (node (ref "U24") (pin "11") (pinfunction "RF_IN_11") (pintype "passive"))
      (node (ref "U33") (pin "5") (pinfunction "IN_5") (pintype "passive"))
    )
    (net (code "63") (name "Net-(U24-RXD)") (class "Default")
      (node (ref "FB5") (pin "2") (pinfunction "2_2") (pintype "passive"))
      (node (ref "U24") (pin "3") (pinfunction "RXD_3") (pintype "input"))
    )
    (net (code "64") (name "Net-(U24-TIMEPULSE)") (class "Default")
      (node (ref "FB8") (pin "2") (pinfunction "2_2") (pintype "passive"))
      (node (ref "U24") (pin "4") (pinfunction "TIMEPULSE_4") (pintype "output"))
    )
    (net (code "65") (name "Net-(U24-TXD)") (class "Default")
      (node (ref "FB6") (pin "2") (pinfunction "2_2") (pintype "passive"))
      (node (ref "U24") (pin "2") (pinfunction "TXD_2") (pintype "output"))
    )
    (net (code "66") (name "Net-(U24-VCC)") (class "Default")
      (node (ref "C100") (pin "1") (pinfunction "1_1") (pintype "passive"))
      (node (ref "C117") (pin "2") (pinfunction "2_2") (pintype "passive"))
      (node (ref "C96") (pin "2") (pinfunction "2_2") (pintype "passive"))
      (node (ref "C97") (pin "2") (pinfunction "2_2") (pintype "passive"))
      (node (ref "J6") (pin "2") (pinfunction "2_2") (pintype "passive"))
      (node (ref "NC13") (pin "1") (pinfunction "1_1") (pintype "passive"))
      (node (ref "U24") (pin "7") (pinfunction "VCC_IO_7") (pintype "power_in"))
      (node (ref "U24") (pin "8") (pinfunction "VCC_8") (pintype "power_in"))
    )
    (net (code "67") (name "Net-(U24-V_BCKP)") (class "Default")
      (node (ref "C105") (pin "2") (pinfunction "2_2") (pintype "passive"))
      (node (ref "R96") (pin "1") (pinfunction "1_1") (pintype "passive"))
      (node (ref "U24") (pin "6") (pinfunction "V_BCKP_6") (pintype "power_in"))
    )
    (net (code "68") (name "Net-(U25-AI)") (class "Default")
      (node (ref "L2") (pin "1") (pinfunction "1_1") (pintype "passive"))
      (node (ref "U25") (pin "4") (pinfunction "AI_4") (pintype "input"))
    )
    (net (code "69") (name "Net-(U25-AO)") (class "Default")
      (node (ref "C99") (pin "2") (pinfunction "2_2") (pintype "passive"))
      (node (ref "U25") (pin "2") (pinfunction "AO_2") (pintype "output"))
    )
    (net (code "70") (name "Net-(U32-IN)") (class "Default")
      (node (ref "L1") (pin "2") (pinfunction "2_2") (pintype "passive"))
      (node (ref "SWC1") (pin "C") (pinfunction "C_C") (pintype "passive"))
      (node (ref "U32") (pin "5") (pinfunction "IN_5") (pintype "passive"))
    )
    (net (code "71") (name "Net-(U32-OUT2)") (class "Default")
      (node (ref "U32") (pin "3") (pinfunction "OUT2_3") (pintype "passive"))
      (node (ref "U33") (pin "1") (pinfunction "OUT1_1") (pintype "passive"))
    )
    (net (code "72") (name "SARA_1V8") (class "Default")
      (node (ref "C73") (pin "2") (pinfunction "2_2") (pintype "passive"))
      (node (ref "C74") (pin "2") (pinfunction "2_2") (pintype "passive"))
      (node (ref "R18") (pin "1") (pinfunction "1_1") (pintype "passive"))
      (node (ref "U19") (pin "8") (pinfunction "VCC(B)_8") (pintype "power_in"))
      (node (ref "U22") (pin "8") (pinfunction "VCC(B)_8") (pintype "power_in"))
    )
    (net (code "73") (name "VCC_MAX") (class "Default")
      (node (ref "C121") (pin "1") (pinfunction "1_1") (pintype "passive"))
      (node (ref "C122") (pin "2") (pinfunction "2_2") (pintype "passive"))
      (node (ref "C123") (pin "1") (pinfunction "1_1") (pintype "passive"))
      (node (ref "C128") (pin "1") (pinfunction "1_1") (pintype "passive"))
      (node (ref "C77") (pin "1") (pinfunction "1_1") (pintype "passive"))
      (node (ref "C79") (pin "1") (pinfunction "1_1") (pintype "passive"))
      (node (ref "C80") (pin "1") (pinfunction "1_1") (pintype "passive"))
      (node (ref "C81") (pin "1") (pinfunction "1_1") (pintype "passive"))
      (node (ref "J6") (pin "3") (pinfunction "3_3") (pintype "passive"))
      (node (ref "NC13") (pin "2") (pinfunction "2_2") (pintype "passive"))
      (node (ref "Q20") (pin "1") (pinfunction "S1_1") (pintype "passive"))
      (node (ref "Q20") (pin "4") (pinfunction "S2_4") (pintype "passive"))
      (node (ref "R68") (pin "1") (pinfunction "1_1") (pintype "passive"))
      (node (ref "R70") (pin "1") (pinfunction "1_1") (pintype "passive"))
      (node (ref "R84") (pin "1") (pinfunction "1_1") (pintype "passive"))
      (node (ref "R85") (pin "1") (pinfunction "1_1") (pintype "passive"))
      (node (ref "R86") (pin "1") (pinfunction "1_1") (pintype "passive"))
      (node (ref "TP42") (pin "1") (pintype "passive"))
      (node (ref "U19") (pin "1") (pinfunction "VCC(A)_1") (pintype "power_in"))
      (node (ref "U19") (pin "5") (pinfunction "OE_5") (pintype "input"))
      (node (ref "U20") (pin "1") (pinfunction "VCC(A)_1") (pintype "power_in"))
      (node (ref "U21") (pin "1") (pinfunction "VCC(A)_1") (pintype "power_in"))
      (node (ref "U22") (pin "1") (pinfunction "VCC(A)_1") (pintype "power_in"))
      (node (ref "U22") (pin "5") (pinfunction "OE_5") (pintype "input"))
      (node (ref "U29") (pin "4") (pinfunction "VOUT_4") (pintype "power_in"))
    )
    (net (code "74") (name "VCC_MAX_LNA") (class "Default")
      (node (ref "C104") (pin "1") (pinfunction "1_1") (pintype "passive"))
      (node (ref "C106") (pin "2") (pinfunction "2_2") (pintype "passive"))
      (node (ref "C107") (pin "2") (pinfunction "2_2") (pintype "passive"))
      (node (ref "L3") (pin "2") (pinfunction "2_2") (pintype "passive"))
      (node (ref "Q28") (pin "2") (pinfunction "G1_2") (pintype "passive"))
      (node (ref "R129") (pin "2") (pinfunction "2_2") (pintype "passive"))
      (node (ref "TP37") (pin "1") (pintype "passive"))
      (node (ref "U25") (pin "1") (pinfunction "VCC_1") (pintype "power_in"))
      (node (ref "U32") (pin "4") (pinfunction "VCTRL_4") (pintype "power_in"))
    )
    (net (code "75") (name "VCC_MAX_RF") (class "Default")
      (node (ref "C92") (pin "1") (pinfunction "1_1") (pintype "passive"))
      (node (ref "C93") (pin "1") (pinfunction "1_1") (pintype "passive"))
      (node (ref "Q23") (pin "4") (pinfunction "S2_4") (pintype "passive"))
      (node (ref "R109") (pin "2") (pinfunction "2_2") (pintype "passive"))
      (node (ref "R128") (pin "2") (pinfunction "2_2") (pintype "passive"))
      (node (ref "TP39") (pin "1") (pintype "passive"))
      (node (ref "U24") (pin "14") (pinfunction "VCC_RF_14") (pintype "power_in"))
      (node (ref "U32") (pin "6") (pinfunction "VDD_6") (pintype "power_in"))
      (node (ref "U33") (pin "6") (pinfunction "VDD_6") (pintype "power_in"))
    )
    (net (code "76") (name "VDD_NORA") (class "Default")
      (node (ref "C75") (pin "2") (pinfunction "2_2") (pintype "passive"))
      (node (ref "R78") (pin "1") (pinfunction "1_1") (pintype "passive"))
      (node (ref "U21") (pin "8") (pinfunction "VCC(B)_8") (pintype "power_in"))
    )
    (net (code "77") (name "unconnected-(Q27B-D2-Pad3)") (class "Default")
      (node (ref "Q27") (pin "3") (pinfunction "D2_3") (pintype "passive+no_connect"))
    )
    (net (code "78") (name "unconnected-(Q28B-D2-Pad3)") (class "Default")
      (node (ref "Q28") (pin "3") (pinfunction "D2_3") (pintype "passive+no_connect"))
    )
    (net (code "79") (name "unconnected-(U24-V_ANT{slash}RSVD-Pad15)") (class "Default")
      (node (ref "U24") (pin "15") (pinfunction "V_ANT/RSVD_15") (pintype "passive+no_connect"))
    )
  )
)
